# simple_breakout.net
KiCad netlist of a schematic drawn in EAGLE
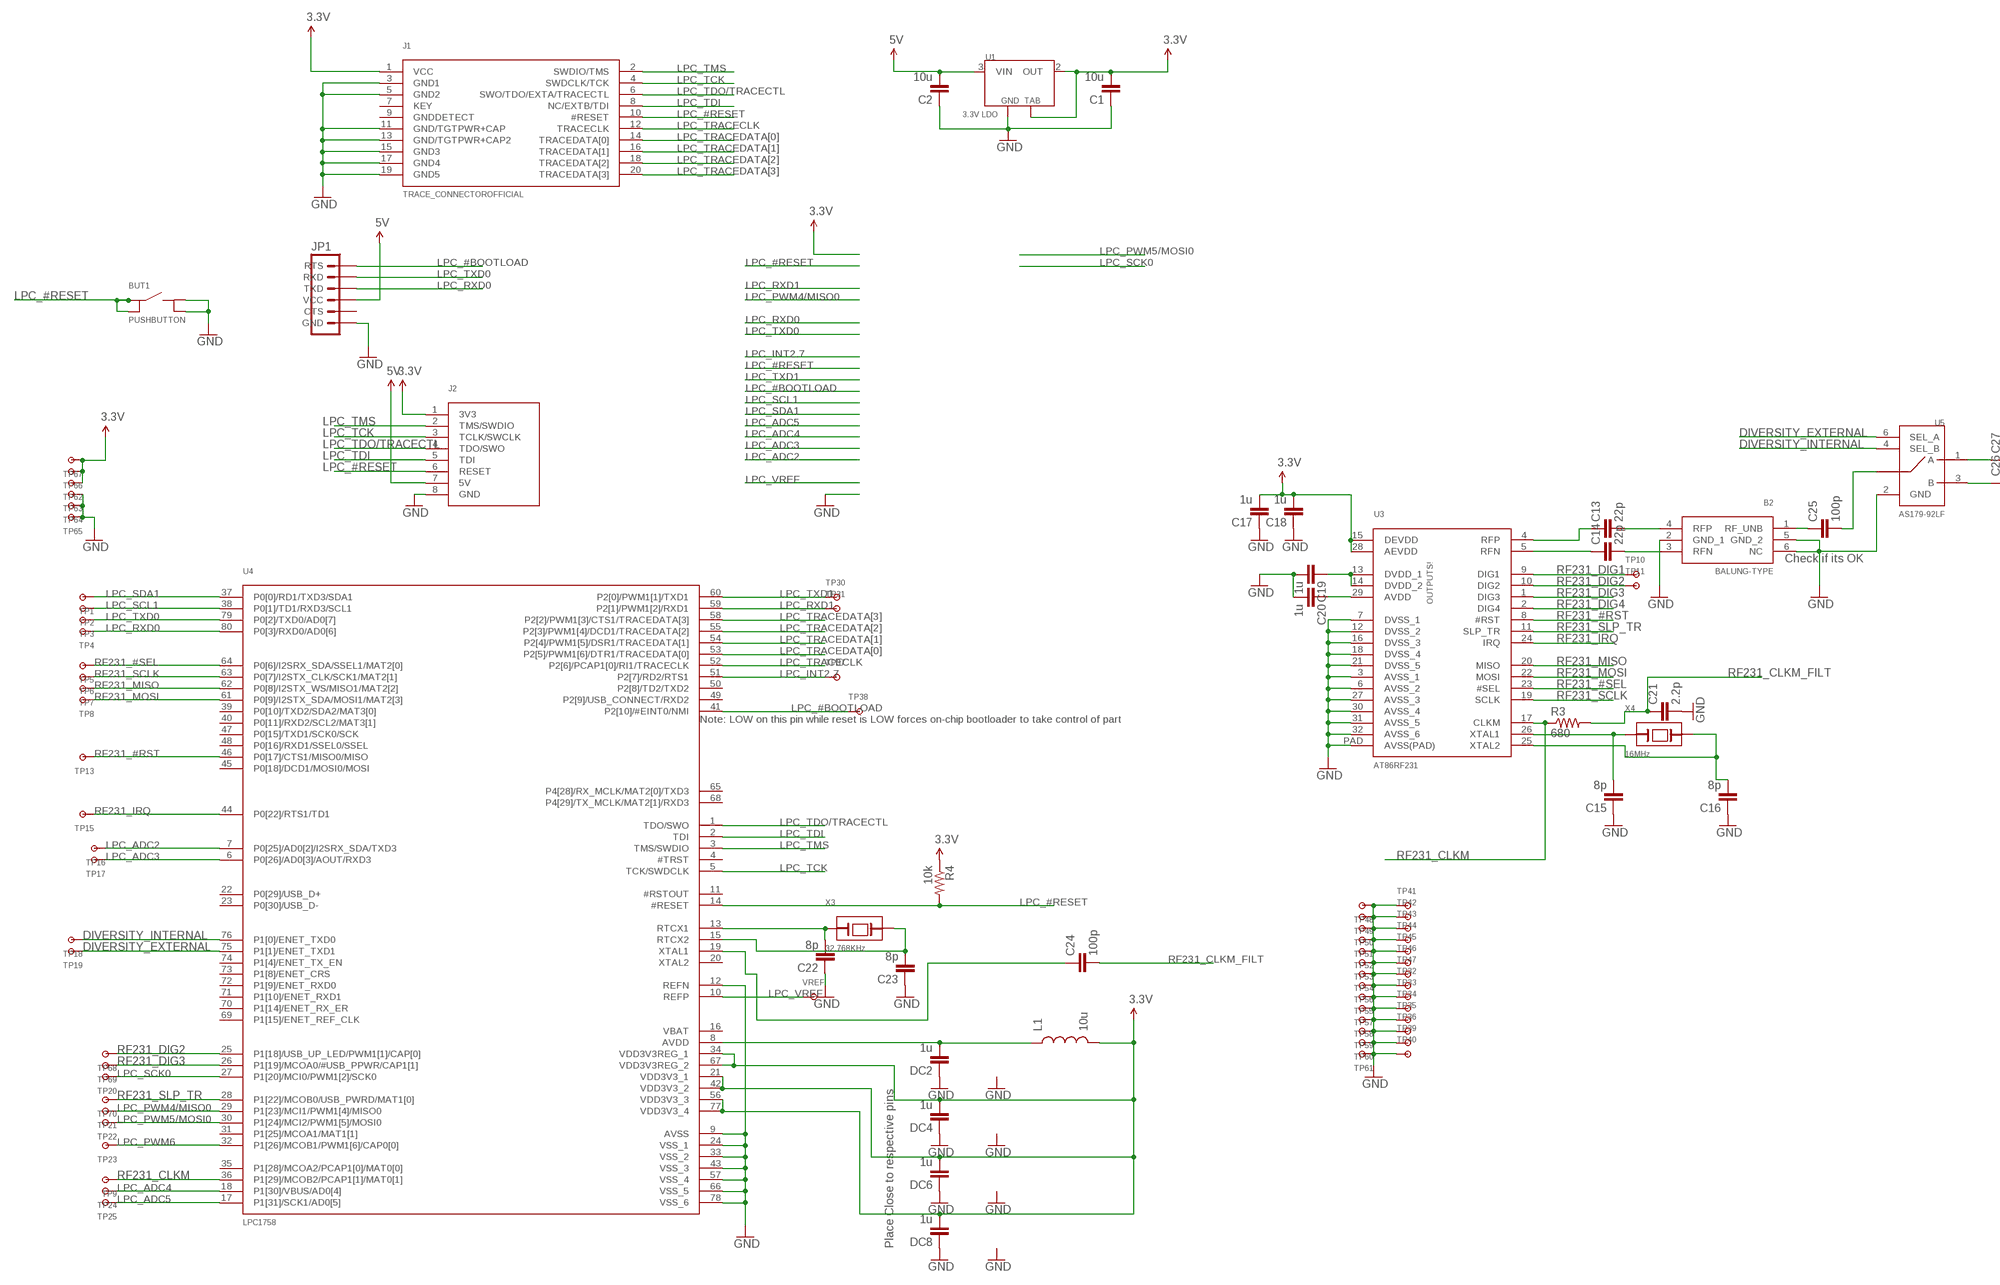
[diagram p0: schematic, sheet 1, part 1 of 2]
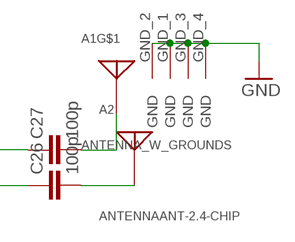
[diagram p1: schematic, sheet 1, part 2 of 2]

(export (version "E")
  (design (tool "Eeschema 10.0.6"))
  (components
    (comp (ref "A1")
      (value "ANTENNA_W_GROUNDS")
      (footprint "eagle-import:CONREVSMA003.031")
      (libsource (lib "eagle-import") (part "ANTENNA_W_GROUNDS"))
    )
    (comp (ref "A2")
      (value "ANTENNAANT-2.4-CHIP")
      (footprint "eagle-import:ANT-2.4-CHP")
      (libsource (lib "eagle-import") (part "ANTENNAANT-2.4-CHIP"))
    )
    (comp (ref "B2")
      (value "BALUNG-TYPE")
      (footprint "eagle-import:MURATA_LDB_BALUN")
      (libsource (lib "eagle-import") (part "BALUNG-TYPE"))
    )
    (comp (ref "BUT1")
      (value "PUSHBUTTON")
      (footprint "eagle-import:SMT_PUSHBUTTON")
      (libsource (lib "eagle-import") (part "PUSHBUTTON"))
    )
    (comp (ref "C1")
      (value "10u")
      (footprint "eagle-import:0805")
      (libsource (lib "eagle-import") (part "CAP0805"))
    )
    (comp (ref "C2")
      (value "10u")
      (footprint "eagle-import:0805")
      (libsource (lib "eagle-import") (part "CAP0805"))
    )
    (comp (ref "C13")
      (value "22p")
      (footprint "eagle-import:C0402")
      (libsource (lib "eagle-import") (part "CAP0402"))
    )
    (comp (ref "C14")
      (value "22p")
      (footprint "eagle-import:C0402")
      (libsource (lib "eagle-import") (part "CAP0402"))
    )
    (comp (ref "C15")
      (value "8p")
      (footprint "eagle-import:C0402")
      (libsource (lib "eagle-import") (part "CAP0402"))
    )
    (comp (ref "C16")
      (value "8p")
      (footprint "eagle-import:C0402")
      (libsource (lib "eagle-import") (part "CAP0402"))
    )
    (comp (ref "C17")
      (value "1u")
      (footprint "eagle-import:C0402")
      (libsource (lib "eagle-import") (part "CAP0402"))
    )
    (comp (ref "C18")
      (value "1u")
      (footprint "eagle-import:C0402")
      (libsource (lib "eagle-import") (part "CAP0402"))
    )
    (comp (ref "C19")
      (value "1u")
      (footprint "eagle-import:C0402")
      (libsource (lib "eagle-import") (part "CAP0402"))
    )
    (comp (ref "C20")
      (value "1u")
      (footprint "eagle-import:C0402")
      (libsource (lib "eagle-import") (part "CAP0402"))
    )
    (comp (ref "C21")
      (value "2.2p")
      (footprint "eagle-import:C0402")
      (libsource (lib "eagle-import") (part "CAP0402"))
    )
    (comp (ref "C22")
      (value "8p")
      (footprint "eagle-import:C0402")
      (libsource (lib "eagle-import") (part "CAP0402"))
    )
    (comp (ref "C23")
      (value "8p")
      (footprint "eagle-import:C0402")
      (libsource (lib "eagle-import") (part "CAP0402"))
    )
    (comp (ref "C24")
      (value "100p")
      (footprint "eagle-import:C0402")
      (libsource (lib "eagle-import") (part "CAP0402"))
    )
    (comp (ref "C25")
      (value "100p")
      (footprint "eagle-import:C0402")
      (libsource (lib "eagle-import") (part "CAP0402"))
    )
    (comp (ref "C26")
      (value "100p")
      (footprint "eagle-import:C0402")
      (libsource (lib "eagle-import") (part "CAP0402"))
    )
    (comp (ref "C27")
      (value "100p")
      (footprint "eagle-import:C0402")
      (libsource (lib "eagle-import") (part "CAP0402"))
    )
    (comp (ref "DC2")
      (value "1u")
      (footprint "eagle-import:C0402")
      (libsource (lib "eagle-import") (part "CAP0402"))
    )
    (comp (ref "DC4")
      (value "1u")
      (footprint "eagle-import:C0402")
      (libsource (lib "eagle-import") (part "CAP0402"))
    )
    (comp (ref "DC6")
      (value "1u")
      (footprint "eagle-import:C0402")
      (libsource (lib "eagle-import") (part "CAP0402"))
    )
    (comp (ref "DC8")
      (value "1u")
      (footprint "eagle-import:C0402")
      (libsource (lib "eagle-import") (part "CAP0402"))
    )
    (comp (ref "J1")
      (value "TRACE_CONNECTOROFFICIAL")
      (footprint "eagle-import:FTSH-110-01-L-DV")
      (libsource (lib "eagle-import") (part "TRACE_CONNECTOROFFICIAL"))
    )
    (comp (ref "J2")
      (value "LPCXPRESSO_JTAG")
      (footprint "eagle-import:1X08")
      (libsource (lib "eagle-import") (part "LPCXPRESSO_JTAG"))
    )
    (comp (ref "JP1")
      (value "FTDI_CABLESIP")
      (footprint "eagle-import:1X06")
      (libsource (lib "eagle-import") (part "FTDI_CABLESIP"))
    )
    (comp (ref "L1")
      (value "10u")
      (footprint "eagle-import:0603")
      (libsource (lib "eagle-import") (part "INDUCTOR0603"))
    )
    (comp (ref "R3")
      (value "680")
      (footprint "eagle-import:C0402")
      (libsource (lib "eagle-import") (part "RESISTOR0402"))
    )
    (comp (ref "R4")
      (value "10k")
      (footprint "eagle-import:C0402")
      (libsource (lib "eagle-import") (part "RESISTOR0402"))
    )
    (comp (ref "TP1")
      (value "TESTPOINT100MIL")
      (footprint "eagle-import:TESTPOINT-100MIL")
      (libsource (lib "eagle-import") (part "TESTPOINT100MIL"))
    )
    (comp (ref "TP2")
      (value "TESTPOINT100MIL")
      (footprint "eagle-import:TESTPOINT-100MIL")
      (libsource (lib "eagle-import") (part "TESTPOINT100MIL"))
    )
    (comp (ref "TP3")
      (value "TESTPOINT100MIL")
      (footprint "eagle-import:TESTPOINT-100MIL")
      (libsource (lib "eagle-import") (part "TESTPOINT100MIL"))
    )
    (comp (ref "TP4")
      (value "TESTPOINT100MIL")
      (footprint "eagle-import:TESTPOINT-100MIL")
      (libsource (lib "eagle-import") (part "TESTPOINT100MIL"))
    )
    (comp (ref "TP5")
      (value "TESTPOINT100MIL")
      (footprint "eagle-import:TESTPOINT-100MIL")
      (libsource (lib "eagle-import") (part "TESTPOINT100MIL"))
    )
    (comp (ref "TP6")
      (value "TESTPOINT100MIL")
      (footprint "eagle-import:TESTPOINT-100MIL")
      (libsource (lib "eagle-import") (part "TESTPOINT100MIL"))
    )
    (comp (ref "TP7")
      (value "TESTPOINT100MIL")
      (footprint "eagle-import:TESTPOINT-100MIL")
      (libsource (lib "eagle-import") (part "TESTPOINT100MIL"))
    )
    (comp (ref "TP8")
      (value "TESTPOINT100MIL")
      (footprint "eagle-import:TESTPOINT-100MIL")
      (libsource (lib "eagle-import") (part "TESTPOINT100MIL"))
    )
    (comp (ref "TP9")
      (value "TESTPOINT100MIL")
      (footprint "eagle-import:TESTPOINT-100MIL")
      (libsource (lib "eagle-import") (part "TESTPOINT100MIL"))
    )
    (comp (ref "TP10")
      (value "TESTPOINT100MIL")
      (footprint "eagle-import:TESTPOINT-100MIL")
      (libsource (lib "eagle-import") (part "TESTPOINT100MIL"))
    )
    (comp (ref "TP11")
      (value "TESTPOINT100MIL")
      (footprint "eagle-import:TESTPOINT-100MIL")
      (libsource (lib "eagle-import") (part "TESTPOINT100MIL"))
    )
    (comp (ref "TP13")
      (value "TESTPOINT100MIL")
      (footprint "eagle-import:TESTPOINT-100MIL")
      (libsource (lib "eagle-import") (part "TESTPOINT100MIL"))
    )
    (comp (ref "TP15")
      (value "TESTPOINT100MIL")
      (footprint "eagle-import:TESTPOINT-100MIL")
      (libsource (lib "eagle-import") (part "TESTPOINT100MIL"))
    )
    (comp (ref "TP16")
      (value "TESTPOINT100MIL")
      (footprint "eagle-import:TESTPOINT-100MIL")
      (libsource (lib "eagle-import") (part "TESTPOINT100MIL"))
    )
    (comp (ref "TP17")
      (value "TESTPOINT100MIL")
      (footprint "eagle-import:TESTPOINT-100MIL")
      (libsource (lib "eagle-import") (part "TESTPOINT100MIL"))
    )
    (comp (ref "TP18")
      (value "TESTPOINT100MIL")
      (footprint "eagle-import:TESTPOINT-100MIL")
      (libsource (lib "eagle-import") (part "TESTPOINT100MIL"))
    )
    (comp (ref "TP19")
      (value "TESTPOINT100MIL")
      (footprint "eagle-import:TESTPOINT-100MIL")
      (libsource (lib "eagle-import") (part "TESTPOINT100MIL"))
    )
    (comp (ref "TP20")
      (value "TESTPOINT100MIL")
      (footprint "eagle-import:TESTPOINT-100MIL")
      (libsource (lib "eagle-import") (part "TESTPOINT100MIL"))
    )
    (comp (ref "TP21")
      (value "TESTPOINT100MIL")
      (footprint "eagle-import:TESTPOINT-100MIL")
      (libsource (lib "eagle-import") (part "TESTPOINT100MIL"))
    )
    (comp (ref "TP22")
      (value "TESTPOINT100MIL")
      (footprint "eagle-import:TESTPOINT-100MIL")
      (libsource (lib "eagle-import") (part "TESTPOINT100MIL"))
    )
    (comp (ref "TP23")
      (value "TESTPOINT100MIL")
      (footprint "eagle-import:TESTPOINT-100MIL")
      (libsource (lib "eagle-import") (part "TESTPOINT100MIL"))
    )
    (comp (ref "TP24")
      (value "TESTPOINT100MIL")
      (footprint "eagle-import:TESTPOINT-100MIL")
      (libsource (lib "eagle-import") (part "TESTPOINT100MIL"))
    )
    (comp (ref "TP25")
      (value "TESTPOINT100MIL")
      (footprint "eagle-import:TESTPOINT-100MIL")
      (libsource (lib "eagle-import") (part "TESTPOINT100MIL"))
    )
    (comp (ref "TP30")
      (value "TESTPOINT100MIL")
      (footprint "eagle-import:TESTPOINT-100MIL")
      (libsource (lib "eagle-import") (part "TESTPOINT100MIL"))
    )
    (comp (ref "TP31")
      (value "TESTPOINT100MIL")
      (footprint "eagle-import:TESTPOINT-100MIL")
      (libsource (lib "eagle-import") (part "TESTPOINT100MIL"))
    )
    (comp (ref "TP32")
      (value "TESTPOINTSMALLEST")
      (footprint "eagle-import:TESTPOINT")
      (libsource (lib "eagle-import") (part "TESTPOINTSMALLEST"))
    )
    (comp (ref "TP33")
      (value "TESTPOINTSMALLEST")
      (footprint "eagle-import:TESTPOINT")
      (libsource (lib "eagle-import") (part "TESTPOINTSMALLEST"))
    )
    (comp (ref "TP34")
      (value "TESTPOINTSMALLEST")
      (footprint "eagle-import:TESTPOINT")
      (libsource (lib "eagle-import") (part "TESTPOINTSMALLEST"))
    )
    (comp (ref "TP35")
      (value "TESTPOINTSMALLEST")
      (footprint "eagle-import:TESTPOINT")
      (libsource (lib "eagle-import") (part "TESTPOINTSMALLEST"))
    )
    (comp (ref "TP36")
      (value "TESTPOINTSMALLEST")
      (footprint "eagle-import:TESTPOINT")
      (libsource (lib "eagle-import") (part "TESTPOINTSMALLEST"))
    )
    (comp (ref "TP37")
      (value "TESTPOINT100MIL")
      (footprint "eagle-import:TESTPOINT-100MIL")
      (libsource (lib "eagle-import") (part "TESTPOINT100MIL"))
    )
    (comp (ref "TP38")
      (value "TESTPOINT100MIL")
      (footprint "eagle-import:TESTPOINT-100MIL")
      (libsource (lib "eagle-import") (part "TESTPOINT100MIL"))
    )
    (comp (ref "TP39")
      (value "TESTPOINTSMALLEST")
      (footprint "eagle-import:TESTPOINT")
      (libsource (lib "eagle-import") (part "TESTPOINTSMALLEST"))
    )
    (comp (ref "TP40")
      (value "TESTPOINTSMALLEST")
      (footprint "eagle-import:TESTPOINT")
      (libsource (lib "eagle-import") (part "TESTPOINTSMALLEST"))
    )
    (comp (ref "TP41")
      (value "TESTPOINTSMALLEST")
      (footprint "eagle-import:TESTPOINT")
      (libsource (lib "eagle-import") (part "TESTPOINTSMALLEST"))
    )
    (comp (ref "TP42")
      (value "TESTPOINTSMALLEST")
      (footprint "eagle-import:TESTPOINT")
      (libsource (lib "eagle-import") (part "TESTPOINTSMALLEST"))
    )
    (comp (ref "TP43")
      (value "TESTPOINTSMALLEST")
      (footprint "eagle-import:TESTPOINT")
      (libsource (lib "eagle-import") (part "TESTPOINTSMALLEST"))
    )
    (comp (ref "TP44")
      (value "TESTPOINTSMALLEST")
      (footprint "eagle-import:TESTPOINT")
      (libsource (lib "eagle-import") (part "TESTPOINTSMALLEST"))
    )
    (comp (ref "TP45")
      (value "TESTPOINTSMALLEST")
      (footprint "eagle-import:TESTPOINT")
      (libsource (lib "eagle-import") (part "TESTPOINTSMALLEST"))
    )
    (comp (ref "TP46")
      (value "TESTPOINTSMALLEST")
      (footprint "eagle-import:TESTPOINT")
      (libsource (lib "eagle-import") (part "TESTPOINTSMALLEST"))
    )
    (comp (ref "TP47")
      (value "TESTPOINTSMALLEST")
      (footprint "eagle-import:TESTPOINT")
      (libsource (lib "eagle-import") (part "TESTPOINTSMALLEST"))
    )
    (comp (ref "TP48")
      (value "TESTPOINTSMALLEST")
      (footprint "eagle-import:TESTPOINT")
      (libsource (lib "eagle-import") (part "TESTPOINTSMALLEST"))
    )
    (comp (ref "TP49")
      (value "TESTPOINTSMALLEST")
      (footprint "eagle-import:TESTPOINT")
      (libsource (lib "eagle-import") (part "TESTPOINTSMALLEST"))
    )
    (comp (ref "TP50")
      (value "TESTPOINTSMALLEST")
      (footprint "eagle-import:TESTPOINT")
      (libsource (lib "eagle-import") (part "TESTPOINTSMALLEST"))
    )
    (comp (ref "TP51")
      (value "TESTPOINTSMALLEST")
      (footprint "eagle-import:TESTPOINT")
      (libsource (lib "eagle-import") (part "TESTPOINTSMALLEST"))
    )
    (comp (ref "TP52")
      (value "TESTPOINTSMALLEST")
      (footprint "eagle-import:TESTPOINT")
      (libsource (lib "eagle-import") (part "TESTPOINTSMALLEST"))
    )
    (comp (ref "TP53")
      (value "TESTPOINTSMALLEST")
      (footprint "eagle-import:TESTPOINT")
      (libsource (lib "eagle-import") (part "TESTPOINTSMALLEST"))
    )
    (comp (ref "TP54")
      (value "TESTPOINTSMALLEST")
      (footprint "eagle-import:TESTPOINT")
      (libsource (lib "eagle-import") (part "TESTPOINTSMALLEST"))
    )
    (comp (ref "TP55")
      (value "TESTPOINTSMALLEST")
      (footprint "eagle-import:TESTPOINT")
      (libsource (lib "eagle-import") (part "TESTPOINTSMALLEST"))
    )
    (comp (ref "TP56")
      (value "TESTPOINTSMALLEST")
      (footprint "eagle-import:TESTPOINT")
      (libsource (lib "eagle-import") (part "TESTPOINTSMALLEST"))
    )
    (comp (ref "TP57")
      (value "TESTPOINTSMALLEST")
      (footprint "eagle-import:TESTPOINT")
      (libsource (lib "eagle-import") (part "TESTPOINTSMALLEST"))
    )
    (comp (ref "TP58")
      (value "TESTPOINTSMALLEST")
      (footprint "eagle-import:TESTPOINT")
      (libsource (lib "eagle-import") (part "TESTPOINTSMALLEST"))
    )
    (comp (ref "TP59")
      (value "TESTPOINTSMALLEST")
      (footprint "eagle-import:TESTPOINT")
      (libsource (lib "eagle-import") (part "TESTPOINTSMALLEST"))
    )
    (comp (ref "TP60")
      (value "TESTPOINTSMALLEST")
      (footprint "eagle-import:TESTPOINT")
      (libsource (lib "eagle-import") (part "TESTPOINTSMALLEST"))
    )
    (comp (ref "TP61")
      (value "TESTPOINTSMALLEST")
      (footprint "eagle-import:TESTPOINT")
      (libsource (lib "eagle-import") (part "TESTPOINTSMALLEST"))
    )
    (comp (ref "TP62")
      (value "TESTPOINT100MIL")
      (footprint "eagle-import:TESTPOINT-100MIL")
      (libsource (lib "eagle-import") (part "TESTPOINT100MIL"))
    )
    (comp (ref "TP63")
      (value "TESTPOINT100MIL")
      (footprint "eagle-import:TESTPOINT-100MIL")
      (libsource (lib "eagle-import") (part "TESTPOINT100MIL"))
    )
    (comp (ref "TP64")
      (value "TESTPOINT100MIL")
      (footprint "eagle-import:TESTPOINT-100MIL")
      (libsource (lib "eagle-import") (part "TESTPOINT100MIL"))
    )
    (comp (ref "TP65")
      (value "TESTPOINT100MIL")
      (footprint "eagle-import:TESTPOINT-100MIL")
      (libsource (lib "eagle-import") (part "TESTPOINT100MIL"))
    )
    (comp (ref "TP66")
      (value "TESTPOINT100MIL")
      (footprint "eagle-import:TESTPOINT-100MIL")
      (libsource (lib "eagle-import") (part "TESTPOINT100MIL"))
    )
    (comp (ref "TP67")
      (value "TESTPOINT100MIL")
      (footprint "eagle-import:TESTPOINT-100MIL")
      (libsource (lib "eagle-import") (part "TESTPOINT100MIL"))
    )
    (comp (ref "TP68")
      (value "TESTPOINT100MIL")
      (footprint "eagle-import:TESTPOINT-100MIL")
      (libsource (lib "eagle-import") (part "TESTPOINT100MIL"))
    )
    (comp (ref "TP69")
      (value "TESTPOINT100MIL")
      (footprint "eagle-import:TESTPOINT-100MIL")
      (libsource (lib "eagle-import") (part "TESTPOINT100MIL"))
    )
    (comp (ref "TP70")
      (value "TESTPOINT100MIL")
      (footprint "eagle-import:TESTPOINT-100MIL")
      (libsource (lib "eagle-import") (part "TESTPOINT100MIL"))
    )
    (comp (ref "U1")
      (value "3.3V LDO")
      (footprint "eagle-import:SOT223")
      (libsource (lib "eagle-import") (part "NX1117C"))
    )
    (comp (ref "U3")
      (value "AT86RF231")
      (footprint "eagle-import:ATRF231_32QN2")
      (libsource (lib "eagle-import") (part "AT86RF231"))
    )
    (comp (ref "U4")
      (value "LPC1758")
      (footprint "eagle-import:LPC1758_LQFP80")
      (libsource (lib "eagle-import") (part "LPC1758"))
    )
    (comp (ref "U5")
      (value "AS179-92LF")
      (footprint "eagle-import:SC-70")
      (libsource (lib "eagle-import") (part "AS179-92LF"))
    )
    (comp (ref "VREF")
      (value "TESTPOINT100MIL")
      (footprint "eagle-import:TESTPOINT-100MIL")
      (libsource (lib "eagle-import") (part "TESTPOINT100MIL"))
    )
    (comp (ref "X3")
      (value "32.768KHz")
      (footprint "eagle-import:ABS07")
      (libsource (lib "eagle-import") (part "XTALABS07"))
    )
    (comp (ref "X4")
      (value "16MHz")
      (footprint "eagle-import:CX3225SA")
      (libsource (lib "eagle-import") (part "XTALCX3225SA"))
    )
  )
  (nets
    (net (code "1") (name "/DIVERSITY_EXTERNAL") (class "Default")
      (node (ref "TP19") (pin "2") (pinfunction "P$1_2") (pintype "bidirectional"))
      (node (ref "U4") (pin "75") (pinfunction "P1[1]/ENET_TXD1_75") (pintype "bidirectional"))
      (node (ref "U5") (pin "6") (pinfunction "SEL_A_6") (pintype "bidirectional"))
    )
    (net (code "2") (name "/DIVERSITY_INTERNAL") (class "Default")
      (node (ref "TP18") (pin "2") (pinfunction "P$1_2") (pintype "bidirectional"))
      (node (ref "U4") (pin "76") (pinfunction "P1[0]/ENET_TXD0_76") (pintype "bidirectional"))
      (node (ref "U5") (pin "4") (pinfunction "SEL_B_4") (pintype "bidirectional"))
    )
    (net (code "3") (name "/LPC_#BOOTLOAD") (class "Default")
      (node (ref "JP1") (pin "6") (pinfunction "RTS_6") (pintype "passive"))
      (node (ref "TP38") (pin "2") (pinfunction "P$1_2") (pintype "bidirectional"))
      (node (ref "U4") (pin "41") (pinfunction "P2[10]/#EINT0/NMI_41") (pintype "bidirectional"))
    )
    (net (code "4") (name "/LPC_#RESET") (class "Default")
      (node (ref "BUT1") (pin "1@1") (pinfunction "1_1@1") (pintype "bidirectional"))
      (node (ref "BUT1") (pin "1@2") (pinfunction "1_1@2") (pintype "bidirectional"))
      (node (ref "J1") (pin "10") (pinfunction "#RESET_10") (pintype "bidirectional"))
      (node (ref "J2") (pin "6") (pinfunction "RESET_6") (pintype "bidirectional"))
      (node (ref "R4") (pin "2") (pinfunction "2_2") (pintype "passive"))
      (node (ref "U4") (pin "14") (pinfunction "#RESET_14") (pintype "bidirectional"))
    )
    (net (code "5") (name "/LPC_ADC2") (class "Default")
      (node (ref "TP16") (pin "2") (pinfunction "P$1_2") (pintype "bidirectional"))
      (node (ref "U4") (pin "7") (pinfunction "P0[25]/AD0[2]/I2SRX_SDA/TXD3_7") (pintype "bidirectional"))
    )
    (net (code "6") (name "/LPC_ADC3") (class "Default")
      (node (ref "TP17") (pin "2") (pinfunction "P$1_2") (pintype "bidirectional"))
      (node (ref "U4") (pin "6") (pinfunction "P0[26]/AD0[3]/AOUT/RXD3_6") (pintype "bidirectional"))
    )
    (net (code "7") (name "/LPC_ADC4") (class "Default")
      (node (ref "TP24") (pin "2") (pinfunction "P$1_2") (pintype "bidirectional"))
      (node (ref "U4") (pin "18") (pinfunction "P1[30]/VBUS/AD0[4]_18") (pintype "bidirectional"))
    )
    (net (code "8") (name "/LPC_ADC5") (class "Default")
      (node (ref "TP25") (pin "2") (pinfunction "P$1_2") (pintype "bidirectional"))
      (node (ref "U4") (pin "17") (pinfunction "P1[31]/SCK1/AD0[5]_17") (pintype "bidirectional"))
    )
    (net (code "9") (name "/LPC_INT2.7") (class "Default")
      (node (ref "TP37") (pin "2") (pinfunction "P$1_2") (pintype "bidirectional"))
      (node (ref "U4") (pin "51") (pinfunction "P2[7]/RD2/RTS1_51") (pintype "bidirectional"))
    )
    (net (code "10") (name "/LPC_PWM4{slash}MISO0") (class "Default")
      (node (ref "TP21") (pin "2") (pinfunction "P$1_2") (pintype "bidirectional"))
      (node (ref "U4") (pin "29") (pinfunction "P1[23]/MCI1/PWM1[4]/MISO0_29") (pintype "bidirectional"))
    )
    (net (code "11") (name "/LPC_PWM5{slash}MOSI0") (class "Default")
      (node (ref "TP22") (pin "2") (pinfunction "P$1_2") (pintype "bidirectional"))
      (node (ref "U4") (pin "30") (pinfunction "P1[24]/MCI2/PWM1[5]/MOSI0_30") (pintype "bidirectional"))
    )
    (net (code "12") (name "/LPC_PWM6") (class "Default")
      (node (ref "TP23") (pin "2") (pinfunction "P$1_2") (pintype "bidirectional"))
      (node (ref "U4") (pin "32") (pinfunction "P1[26]/MCOB1/PWM1[6]/CAP0[0]_32") (pintype "bidirectional"))
    )
    (net (code "13") (name "/LPC_RXD0") (class "Default")
      (node (ref "JP1") (pin "4") (pinfunction "TXD_4") (pintype "passive"))
      (node (ref "TP4") (pin "2") (pinfunction "P$1_2") (pintype "bidirectional"))
      (node (ref "U4") (pin "80") (pinfunction "P0[3]/RXD0/AD0[6]_80") (pintype "bidirectional"))
    )
    (net (code "14") (name "/LPC_RXD1") (class "Default")
      (node (ref "TP31") (pin "2") (pinfunction "P$1_2") (pintype "bidirectional"))
      (node (ref "U4") (pin "59") (pinfunction "P2[1]/PWM1[2]/RXD1_59") (pintype "bidirectional"))
    )
    (net (code "15") (name "/LPC_SCK0") (class "Default")
      (node (ref "TP20") (pin "2") (pinfunction "P$1_2") (pintype "bidirectional"))
      (node (ref "U4") (pin "27") (pinfunction "P1[20]/MCI0/PWM1[2]/SCK0_27") (pintype "bidirectional"))
    )
    (net (code "16") (name "/LPC_SCL1") (class "Default")
      (node (ref "TP2") (pin "2") (pinfunction "P$1_2") (pintype "bidirectional"))
      (node (ref "U4") (pin "38") (pinfunction "P0[1]/TD1/RXD3/SCL1_38") (pintype "bidirectional"))
    )
    (net (code "17") (name "/LPC_SDA1") (class "Default")
      (node (ref "TP1") (pin "2") (pinfunction "P$1_2") (pintype "bidirectional"))
      (node (ref "U4") (pin "37") (pinfunction "P0[0]/RD1/TXD3/SDA1_37") (pintype "bidirectional"))
    )
    (net (code "18") (name "/LPC_TCK") (class "Default")
      (node (ref "J1") (pin "4") (pinfunction "SWDCLK/TCK_4") (pintype "bidirectional"))
      (node (ref "J2") (pin "3") (pinfunction "TCLK/SWCLK_3") (pintype "bidirectional"))
      (node (ref "U4") (pin "5") (pinfunction "TCK/SWDCLK_5") (pintype "bidirectional"))
    )
    (net (code "19") (name "/LPC_TDI") (class "Default")
      (node (ref "J1") (pin "8") (pinfunction "NC/EXTB/TDI_8") (pintype "bidirectional"))
      (node (ref "J2") (pin "5") (pinfunction "TDI_5") (pintype "bidirectional"))
      (node (ref "U4") (pin "2") (pinfunction "TDI_2") (pintype "bidirectional"))
    )
    (net (code "20") (name "/LPC_TDO{slash}TRACECTL") (class "Default")
      (node (ref "J1") (pin "6") (pinfunction "SWO/TDO/EXTA/TRACECTL_6") (pintype "bidirectional"))
      (node (ref "J2") (pin "4") (pinfunction "TDO/SWO_4") (pintype "bidirectional"))
      (node (ref "U4") (pin "1") (pinfunction "TDO/SWO_1") (pintype "bidirectional"))
    )
    (net (code "21") (name "/LPC_TMS") (class "Default")
      (node (ref "J1") (pin "2") (pinfunction "SWDIO/TMS_2") (pintype "bidirectional"))
      (node (ref "J2") (pin "2") (pinfunction "TMS/SWDIO_2") (pintype "bidirectional"))
      (node (ref "U4") (pin "3") (pinfunction "TMS/SWDIO_3") (pintype "bidirectional"))
    )
    (net (code "22") (name "/LPC_TRACECLK") (class "Default")
      (node (ref "J1") (pin "12") (pinfunction "TRACECLK_12") (pintype "bidirectional"))
      (node (ref "U4") (pin "52") (pinfunction "P2[6]/PCAP1[0]/RI1/TRACECLK_52") (pintype "bidirectional"))
    )
    (net (code "23") (name "/LPC_TRACEDATA[0]") (class "Default")
      (node (ref "J1") (pin "14") (pinfunction "TRACEDATA[0]_14") (pintype "bidirectional"))
      (node (ref "U4") (pin "53") (pinfunction "P2[5]/PWM1[6]/DTR1/TRACEDATA[0]_53") (pintype "bidirectional"))
    )
    (net (code "24") (name "/LPC_TRACEDATA[1]") (class "Default")
      (node (ref "J1") (pin "16") (pinfunction "TRACEDATA[1]_16") (pintype "bidirectional"))
      (node (ref "U4") (pin "54") (pinfunction "P2[4]/PWM1[5]/DSR1/TRACEDATA[1]_54") (pintype "bidirectional"))
    )
    (net (code "25") (name "/LPC_TRACEDATA[2]") (class "Default")
      (node (ref "J1") (pin "18") (pinfunction "TRACEDATA[2]_18") (pintype "bidirectional"))
      (node (ref "U4") (pin "55") (pinfunction "P2[3]/PWM1[4]/DCD1/TRACEDATA[2]_55") (pintype "bidirectional"))
    )
    (net (code "26") (name "/LPC_TRACEDATA[3]") (class "Default")
      (node (ref "J1") (pin "20") (pinfunction "TRACEDATA[3]_20") (pintype "bidirectional"))
      (node (ref "U4") (pin "58") (pinfunction "P2[2]/PWM1[3]/CTS1/TRACEDATA[3]_58") (pintype "bidirectional"))
    )
    (net (code "27") (name "/LPC_TXD0") (class "Default")
      (node (ref "JP1") (pin "5") (pinfunction "RXD_5") (pintype "passive"))
      (node (ref "TP3") (pin "2") (pinfunction "P$1_2") (pintype "bidirectional"))
      (node (ref "U4") (pin "79") (pinfunction "P0[2]/TXD0/AD0[7]_79") (pintype "bidirectional"))
    )
    (net (code "28") (name "/LPC_TXD1") (class "Default")
      (node (ref "TP30") (pin "2") (pinfunction "P$1_2") (pintype "bidirectional"))
      (node (ref "U4") (pin "60") (pinfunction "P2[0]/PWM1[1]/TXD1_60") (pintype "bidirectional"))
    )
    (net (code "29") (name "/LPC_VREF") (class "Default")
      (node (ref "U4") (pin "10") (pinfunction "REFP_10") (pintype "bidirectional"))
      (node (ref "VREF") (pin "2") (pinfunction "P$1_2") (pintype "bidirectional"))
    )
    (net (code "30") (name "/RF231_#RST") (class "Default")
      (node (ref "TP13") (pin "2") (pinfunction "P$1_2") (pintype "bidirectional"))
      (node (ref "U3") (pin "8") (pinfunction "#RST_8") (pintype "bidirectional"))
      (node (ref "U4") (pin "46") (pinfunction "P0[17]/CTS1/MISO0/MISO_46") (pintype "bidirectional"))
    )
    (net (code "31") (name "/RF231_#SEL") (class "Default")
      (node (ref "TP5") (pin "2") (pinfunction "P$1_2") (pintype "bidirectional"))
      (node (ref "U3") (pin "23") (pinfunction "#SEL_23") (pintype "bidirectional"))
      (node (ref "U4") (pin "64") (pinfunction "P0[6]/I2SRX_SDA/SSEL1/MAT2[0]_64") (pintype "bidirectional"))
    )
    (net (code "32") (name "/RF231_CLKM") (class "Default")
      (node (ref "R3") (pin "1") (pinfunction "1_1") (pintype "passive"))
      (node (ref "TP9") (pin "2") (pinfunction "P$1_2") (pintype "bidirectional"))
      (node (ref "U3") (pin "17") (pinfunction "CLKM_17") (pintype "bidirectional"))
      (node (ref "U4") (pin "36") (pinfunction "P1[29]/MCOB2/PCAP1[1]/MAT0[1]_36") (pintype "bidirectional"))
    )
    (net (code "33") (name "/RF231_CLKM_FILT") (class "Default")
      (node (ref "C21") (pin "1") (pinfunction "1_1") (pintype "passive"))
      (node (ref "C24") (pin "2") (pinfunction "2_2") (pintype "passive"))
      (node (ref "R3") (pin "2") (pinfunction "2_2") (pintype "passive"))
    )
    (net (code "34") (name "/RF231_DIG1") (class "Default")
      (node (ref "TP10") (pin "2") (pinfunction "P$1_2") (pintype "bidirectional"))
      (node (ref "U3") (pin "9") (pinfunction "DIG1_9") (pintype "bidirectional"))
    )
    (net (code "35") (name "/RF231_DIG2") (class "Default")
      (node (ref "TP11") (pin "2") (pinfunction "P$1_2") (pintype "bidirectional"))
      (node (ref "TP68") (pin "2") (pinfunction "P$1_2") (pintype "bidirectional"))
      (node (ref "U3") (pin "10") (pinfunction "DIG2_10") (pintype "bidirectional"))
      (node (ref "U4") (pin "25") (pinfunction "P1[18]/USB_UP_LED/PWM1[1]/CAP[0]_25") (pintype "bidirectional"))
    )
    (net (code "36") (name "/RF231_DIG3") (class "Default")
      (node (ref "TP69") (pin "2") (pinfunction "P$1_2") (pintype "bidirectional"))
      (node (ref "U3") (pin "1") (pinfunction "DIG3_1") (pintype "bidirectional"))
      (node (ref "U4") (pin "26") (pinfunction "P1[19]/MCOA0/#USB_PPWR/CAP1[1]_26") (pintype "bidirectional"))
    )
    (net (code "37") (name "/RF231_DIG4") (class "Default")
      (node (ref "U3") (pin "2") (pinfunction "DIG4_2") (pintype "bidirectional"))
    )
    (net (code "38") (name "/RF231_IRQ") (class "Default")
      (node (ref "TP15") (pin "2") (pinfunction "P$1_2") (pintype "bidirectional"))
      (node (ref "U3") (pin "24") (pinfunction "IRQ_24") (pintype "bidirectional"))
      (node (ref "U4") (pin "44") (pinfunction "P0[22]/RTS1/TD1_44") (pintype "bidirectional"))
    )
    (net (code "39") (name "/RF231_MISO") (class "Default")
      (node (ref "TP7") (pin "2") (pinfunction "P$1_2") (pintype "bidirectional"))
      (node (ref "U3") (pin "20") (pinfunction "MISO_20") (pintype "bidirectional"))
      (node (ref "U4") (pin "62") (pinfunction "P0[8]/I2STX_WS/MISO1/MAT2[2]_62") (pintype "bidirectional"))
    )
    (net (code "40") (name "/RF231_MOSI") (class "Default")
      (node (ref "TP8") (pin "2") (pinfunction "P$1_2") (pintype "bidirectional"))
      (node (ref "U3") (pin "22") (pinfunction "MOSI_22") (pintype "bidirectional"))
      (node (ref "U4") (pin "61") (pinfunction "P0[9]/I2STX_SDA/MOSI1/MAT2[3]_61") (pintype "bidirectional"))
    )
    (net (code "41") (name "/RF231_SCLK") (class "Default")
      (node (ref "TP6") (pin "2") (pinfunction "P$1_2") (pintype "bidirectional"))
      (node (ref "U3") (pin "19") (pinfunction "SCLK_19") (pintype "bidirectional"))
      (node (ref "U4") (pin "63") (pinfunction "P0[7]/I2STX_CLK/SCK1/MAT2[1]_63") (pintype "bidirectional"))
    )
    (net (code "42") (name "/RF231_SLP_TR") (class "Default")
      (node (ref "TP70") (pin "2") (pinfunction "P$1_2") (pintype "bidirectional"))
      (node (ref "U3") (pin "11") (pinfunction "SLP_TR_11") (pintype "bidirectional"))
      (node (ref "U4") (pin "28") (pinfunction "P1[22]/MCOB0/USB_PWRD/MAT1[0]_28") (pintype "bidirectional"))
    )
    (net (code "43") (name "3.3V") (class "Default")
      (node (ref "C1") (pin "2") (pinfunction "2_2") (pintype "passive"))
      (node (ref "C17") (pin "2") (pinfunction "2_2") (pintype "passive"))
      (node (ref "C18") (pin "2") (pinfunction "2_2") (pintype "passive"))
      (node (ref "DC4") (pin "2") (pinfunction "2_2") (pintype "passive"))
      (node (ref "DC6") (pin "2") (pinfunction "2_2") (pintype "passive"))
      (node (ref "DC8") (pin "2") (pinfunction "2_2") (pintype "passive"))
      (node (ref "J1") (pin "1") (pinfunction "VCC_1") (pintype "bidirectional"))
      (node (ref "J2") (pin "1") (pinfunction "3V3_1") (pintype "bidirectional"))
      (node (ref "L1") (pin "2") (pinfunction "2_2") (pintype "passive"))
      (node (ref "R4") (pin "1") (pinfunction "1_1") (pintype "passive"))
      (node (ref "TP62") (pin "2") (pinfunction "P$1_2") (pintype "bidirectional"))
      (node (ref "TP66") (pin "2") (pinfunction "P$1_2") (pintype "bidirectional"))
      (node (ref "TP67") (pin "2") (pinfunction "P$1_2") (pintype "bidirectional"))
      (node (ref "U1") (pin "2") (pinfunction "OUT_2") (pintype "bidirectional"))
      (node (ref "U1") (pin "4") (pinfunction "TAB_4") (pintype "bidirectional"))
      (node (ref "U3") (pin "15") (pinfunction "DEVDD_15") (pintype "bidirectional"))
      (node (ref "U3") (pin "28") (pinfunction "AEVDD_28") (pintype "bidirectional"))
      (node (ref "U4") (pin "21") (pinfunction "VDD3V3_1_21") (pintype "bidirectional"))
      (node (ref "U4") (pin "34") (pinfunction "VDD3V3REG_1_34") (pintype "bidirectional"))
      (node (ref "U4") (pin "42") (pinfunction "VDD3V3_2_42") (pintype "bidirectional"))
      (node (ref "U4") (pin "56") (pinfunction "VDD3V3_3_56") (pintype "bidirectional"))
      (node (ref "U4") (pin "67") (pinfunction "VDD3V3REG_2_67") (pintype "bidirectional"))
      (node (ref "U4") (pin "77") (pinfunction "VDD3V3_4_77") (pintype "bidirectional"))
    )
    (net (code "44") (name "5V") (class "Default")
      (node (ref "C2") (pin "2") (pinfunction "2_2") (pintype "passive"))
      (node (ref "J2") (pin "7") (pinfunction "5V_7") (pintype "bidirectional"))
      (node (ref "JP1") (pin "3") (pinfunction "VCC_3") (pintype "passive"))
      (node (ref "U1") (pin "3") (pinfunction "VIN_3") (pintype "bidirectional"))
    )
    (net (code "45") (name "GND") (class "Default")
      (node (ref "A1") (pin "GND_1") (pinfunction "GND_GND_1") (pintype "power_in"))
      (node (ref "A1") (pin "GND_2") (pinfunction "GND_GND_2") (pintype "power_in"))
      (node (ref "A1") (pin "GND_3") (pinfunction "GND_GND_3") (pintype "power_in"))
      (node (ref "A1") (pin "GND_4") (pinfunction "GND_GND_4") (pintype "power_in"))
      (node (ref "B2") (pin "2") (pinfunction "GND_1_2") (pintype "bidirectional"))
      (node (ref "B2") (pin "5") (pinfunction "GND_2_5") (pintype "bidirectional"))
      (node (ref "B2") (pin "6") (pinfunction "NC_6") (pintype "bidirectional"))
      (node (ref "BUT1") (pin "2@1") (pinfunction "2_2@1") (pintype "bidirectional"))
      (node (ref "BUT1") (pin "2@2") (pinfunction "2_2@2") (pintype "bidirectional"))
      (node (ref "C1") (pin "1") (pinfunction "1_1") (pintype "passive"))
      (node (ref "C15") (pin "1") (pinfunction "1_1") (pintype "passive"))
      (node (ref "C16") (pin "1") (pinfunction "1_1") (pintype "passive"))
      (node (ref "C17") (pin "1") (pinfunction "1_1") (pintype "passive"))
      (node (ref "C18") (pin "1") (pinfunction "1_1") (pintype "passive"))
      (node (ref "C19") (pin "2") (pinfunction "2_2") (pintype "passive"))
      (node (ref "C2") (pin "1") (pinfunction "1_1") (pintype "passive"))
      (node (ref "C20") (pin "2") (pinfunction "2_2") (pintype "passive"))
      (node (ref "C21") (pin "2") (pinfunction "2_2") (pintype "passive"))
      (node (ref "C22") (pin "1") (pinfunction "1_1") (pintype "passive"))
      (node (ref "C23") (pin "1") (pinfunction "1_1") (pintype "passive"))
      (node (ref "DC2") (pin "1") (pinfunction "1_1") (pintype "passive"))
      (node (ref "DC4") (pin "1") (pinfunction "1_1") (pintype "passive"))
      (node (ref "DC6") (pin "1") (pinfunction "1_1") (pintype "passive"))
      (node (ref "DC8") (pin "1") (pinfunction "1_1") (pintype "passive"))
      (node (ref "J1") (pin "11") (pinfunction "GND/TGTPWR+CAP_11") (pintype "bidirectional"))
      (node (ref "J1") (pin "13") (pinfunction "GND/TGTPWR+CAP2_13") (pintype "bidirectional"))
      (node (ref "J1") (pin "15") (pinfunction "GND3_15") (pintype "bidirectional"))
      (node (ref "J1") (pin "17") (pinfunction "GND4_17") (pintype "bidirectional"))
      (node (ref "J1") (pin "19") (pinfunction "GND5_19") (pintype "bidirectional"))
      (node (ref "J1") (pin "3") (pinfunction "GND1_3") (pintype "bidirectional"))
      (node (ref "J1") (pin "5") (pinfunction "GND2_5") (pintype "bidirectional"))
      (node (ref "J2") (pin "8") (pinfunction "GND_8") (pintype "bidirectional"))
      (node (ref "JP1") (pin "1") (pinfunction "GND_1") (pintype "passive"))
      (node (ref "TP32") (pin "P$1") (pinfunction "P$1_P$1") (pintype "bidirectional"))
      (node (ref "TP33") (pin "P$1") (pinfunction "P$1_P$1") (pintype "bidirectional"))
      (node (ref "TP34") (pin "P$1") (pinfunction "P$1_P$1") (pintype "bidirectional"))
      (node (ref "TP35") (pin "P$1") (pinfunction "P$1_P$1") (pintype "bidirectional"))
      (node (ref "TP36") (pin "P$1") (pinfunction "P$1_P$1") (pintype "bidirectional"))
      (node (ref "TP39") (pin "P$1") (pinfunction "P$1_P$1") (pintype "bidirectional"))
      (node (ref "TP40") (pin "P$1") (pinfunction "P$1_P$1") (pintype "bidirectional"))
      (node (ref "TP41") (pin "P$1") (pinfunction "P$1_P$1") (pintype "bidirectional"))
      (node (ref "TP42") (pin "P$1") (pinfunction "P$1_P$1") (pintype "bidirectional"))
      (node (ref "TP43") (pin "P$1") (pinfunction "P$1_P$1") (pintype "bidirectional"))
      (node (ref "TP44") (pin "P$1") (pinfunction "P$1_P$1") (pintype "bidirectional"))
      (node (ref "TP45") (pin "P$1") (pinfunction "P$1_P$1") (pintype "bidirectional"))
      (node (ref "TP46") (pin "P$1") (pinfunction "P$1_P$1") (pintype "bidirectional"))
      (node (ref "TP47") (pin "P$1") (pinfunction "P$1_P$1") (pintype "bidirectional"))
      (node (ref "TP48") (pin "P$1") (pinfunction "P$1_P$1") (pintype "bidirectional"))
      (node (ref "TP49") (pin "P$1") (pinfunction "P$1_P$1") (pintype "bidirectional"))
      (node (ref "TP50") (pin "P$1") (pinfunction "P$1_P$1") (pintype "bidirectional"))
      (node (ref "TP51") (pin "P$1") (pinfunction "P$1_P$1") (pintype "bidirectional"))
      (node (ref "TP52") (pin "P$1") (pinfunction "P$1_P$1") (pintype "bidirectional"))
      (node (ref "TP53") (pin "P$1") (pinfunction "P$1_P$1") (pintype "bidirectional"))
      (node (ref "TP54") (pin "P$1") (pinfunction "P$1_P$1") (pintype "bidirectional"))
      (node (ref "TP55") (pin "P$1") (pinfunction "P$1_P$1") (pintype "bidirectional"))
      (node (ref "TP56") (pin "P$1") (pinfunction "P$1_P$1") (pintype "bidirectional"))
      (node (ref "TP57") (pin "P$1") (pinfunction "P$1_P$1") (pintype "bidirectional"))
      (node (ref "TP58") (pin "P$1") (pinfunction "P$1_P$1") (pintype "bidirectional"))
      (node (ref "TP59") (pin "P$1") (pinfunction "P$1_P$1") (pintype "bidirectional"))
      (node (ref "TP60") (pin "P$1") (pinfunction "P$1_P$1") (pintype "bidirectional"))
      (node (ref "TP61") (pin "P$1") (pinfunction "P$1_P$1") (pintype "bidirectional"))
      (node (ref "TP63") (pin "2") (pinfunction "P$1_2") (pintype "bidirectional"))
      (node (ref "TP64") (pin "2") (pinfunction "P$1_2") (pintype "bidirectional"))
      (node (ref "TP65") (pin "2") (pinfunction "P$1_2") (pintype "bidirectional"))
      (node (ref "U1") (pin "1") (pinfunction "GND_1") (pintype "bidirectional"))
      (node (ref "U3") (pin "12") (pinfunction "DVSS_2_12") (pintype "bidirectional"))
      (node (ref "U3") (pin "16") (pinfunction "DVSS_3_16") (pintype "bidirectional"))
      (node (ref "U3") (pin "18") (pinfunction "DVSS_4_18") (pintype "bidirectional"))
      (node (ref "U3") (pin "21") (pinfunction "DVSS_5_21") (pintype "bidirectional"))
      (node (ref "U3") (pin "27") (pinfunction "AVSS_3_27") (pintype "bidirectional"))
      (node (ref "U3") (pin "3") (pinfunction "AVSS_1_3") (pintype "bidirectional"))
      (node (ref "U3") (pin "30") (pinfunction "AVSS_4_30") (pintype "bidirectional"))
      (node (ref "U3") (pin "31") (pinfunction "AVSS_5_31") (pintype "bidirectional"))
      (node (ref "U3") (pin "32") (pinfunction "AVSS_6_32") (pintype "bidirectional"))
      (node (ref "U3") (pin "6") (pinfunction "AVSS_2_6") (pintype "bidirectional"))
      (node (ref "U3") (pin "7") (pinfunction "DVSS_1_7") (pintype "bidirectional"))
      (node (ref "U3") (pin "PAD") (pinfunction "AVSS(PAD)_PAD") (pintype "bidirectional"))
      (node (ref "U4") (pin "12") (pinfunction "REFN_12") (pintype "bidirectional"))
      (node (ref "U4") (pin "24") (pinfunction "VSS_1_24") (pintype "bidirectional"))
      (node (ref "U4") (pin "33") (pinfunction "VSS_2_33") (pintype "bidirectional"))
      (node (ref "U4") (pin "43") (pinfunction "VSS_3_43") (pintype "bidirectional"))
      (node (ref "U4") (pin "57") (pinfunction "VSS_4_57") (pintype "bidirectional"))
      (node (ref "U4") (pin "66") (pinfunction "VSS_5_66") (pintype "bidirectional"))
      (node (ref "U4") (pin "78") (pinfunction "VSS_6_78") (pintype "bidirectional"))
      (node (ref "U4") (pin "9") (pinfunction "AVSS_9") (pintype "bidirectional"))
      (node (ref "U5") (pin "2") (pinfunction "GND_2") (pintype "bidirectional"))
    )
    (net (code "46") (name "Net-(A1A-P$1)") (class "Default")
      (node (ref "A1") (pin "CON") (pinfunction "P$1_CON") (pintype "bidirectional"))
      (node (ref "C27") (pin "2") (pinfunction "2_2") (pintype "passive"))
    )
    (net (code "47") (name "Net-(A2-P$1)") (class "Default")
      (node (ref "A2") (pin "CON") (pinfunction "P$1_CON") (pintype "bidirectional"))
      (node (ref "C26") (pin "2") (pinfunction "2_2") (pintype "passive"))
    )
    (net (code "48") (name "Net-(B2-RFN)") (class "Default")
      (node (ref "B2") (pin "3") (pinfunction "RFN_3") (pintype "bidirectional"))
      (node (ref "C14") (pin "2") (pinfunction "2_2") (pintype "passive"))
    )
    (net (code "49") (name "Net-(B2-RFP)") (class "Default")
      (node (ref "B2") (pin "4") (pinfunction "RFP_4") (pintype "bidirectional"))
      (node (ref "C13") (pin "2") (pinfunction "2_2") (pintype "passive"))
    )
    (net (code "50") (name "Net-(B2-RF_UNB)") (class "Default")
      (node (ref "B2") (pin "1") (pinfunction "RF_UNB_1") (pintype "bidirectional"))
      (node (ref "C25") (pin "1") (pinfunction "1_1") (pintype "passive"))
    )
    (net (code "51") (name "Net-(U3-AVDD)") (class "Default")
      (node (ref "C20") (pin "1") (pinfunction "1_1") (pintype "passive"))
      (node (ref "U3") (pin "29") (pinfunction "AVDD_29") (pintype "bidirectional"))
    )
    (net (code "52") (name "Net-(U3-DVDD_1)") (class "Default")
      (node (ref "C19") (pin "1") (pinfunction "1_1") (pintype "passive"))
      (node (ref "U3") (pin "13") (pinfunction "DVDD_1_13") (pintype "bidirectional"))
      (node (ref "U3") (pin "14") (pinfunction "DVDD_2_14") (pintype "bidirectional"))
    )
    (net (code "53") (name "Net-(U3-RFN)") (class "Default")
      (node (ref "C14") (pin "1") (pinfunction "1_1") (pintype "passive"))
      (node (ref "U3") (pin "5") (pinfunction "RFN_5") (pintype "bidirectional"))
    )
    (net (code "54") (name "Net-(U3-RFP)") (class "Default")
      (node (ref "C13") (pin "1") (pinfunction "1_1") (pintype "passive"))
      (node (ref "U3") (pin "4") (pinfunction "RFP_4") (pintype "bidirectional"))
    )
    (net (code "55") (name "Net-(U3-XTAL1)") (class "Default")
      (node (ref "C15") (pin "2") (pinfunction "2_2") (pintype "passive"))
      (node (ref "U3") (pin "26") (pinfunction "XTAL1_26") (pintype "bidirectional"))
      (node (ref "X4") (pin "3") (pinfunction "A_3") (pintype "bidirectional"))
    )
    (net (code "56") (name "Net-(U3-XTAL2)") (class "Default")
      (node (ref "C16") (pin "2") (pinfunction "2_2") (pintype "passive"))
      (node (ref "U3") (pin "25") (pinfunction "XTAL2_25") (pintype "bidirectional"))
      (node (ref "X4") (pin "1") (pinfunction "B_1") (pintype "bidirectional"))
    )
    (net (code "57") (name "Net-(U4-AVDD)") (class "Default")
      (node (ref "DC2") (pin "2") (pinfunction "2_2") (pintype "passive"))
      (node (ref "L1") (pin "1") (pinfunction "1_1") (pintype "passive"))
      (node (ref "U4") (pin "8") (pinfunction "AVDD_8") (pintype "bidirectional"))
    )
    (net (code "58") (name "Net-(U4-RTCX1)") (class "Default")
      (node (ref "C22") (pin "2") (pinfunction "2_2") (pintype "passive"))
      (node (ref "U4") (pin "13") (pinfunction "RTCX1_13") (pintype "bidirectional"))
      (node (ref "X3") (pin "1") (pinfunction "A_1") (pintype "bidirectional"))
    )
    (net (code "59") (name "Net-(U4-RTCX2)") (class "Default")
      (node (ref "C23") (pin "2") (pinfunction "2_2") (pintype "passive"))
      (node (ref "U4") (pin "15") (pinfunction "RTCX2_15") (pintype "bidirectional"))
      (node (ref "X3") (pin "2") (pinfunction "B_2") (pintype "bidirectional"))
    )
    (net (code "60") (name "Net-(U4-XTAL1)") (class "Default")
      (node (ref "C24") (pin "1") (pinfunction "1_1") (pintype "passive"))
      (node (ref "U4") (pin "19") (pinfunction "XTAL1_19") (pintype "bidirectional"))
    )
    (net (code "61") (name "Net-(U5-A)") (class "Default")
      (node (ref "C27") (pin "1") (pinfunction "1_1") (pintype "passive"))
      (node (ref "U5") (pin "1") (pinfunction "A_1") (pintype "bidirectional"))
    )
    (net (code "62") (name "Net-(U5-B)") (class "Default")
      (node (ref "C26") (pin "1") (pinfunction "1_1") (pintype "passive"))
      (node (ref "U5") (pin "3") (pinfunction "B_3") (pintype "bidirectional"))
    )
    (net (code "63") (name "Net-(U5-W)") (class "Default")
      (node (ref "C25") (pin "2") (pinfunction "2_2") (pintype "passive"))
      (node (ref "U5") (pin "5") (pinfunction "W_5") (pintype "bidirectional"))
    )
    (net (code "64") (name "unconnected-(J1-GNDDETECT-Pad9)") (class "Default")
      (node (ref "J1") (pin "9") (pinfunction "GNDDETECT_9") (pintype "bidirectional"))
    )
    (net (code "65") (name "unconnected-(J1-KEY-Pad7)") (class "Default")
      (node (ref "J1") (pin "7") (pinfunction "KEY_7") (pintype "bidirectional"))
    )
    (net (code "66") (name "unconnected-(JP1-CTS-Pad2)") (class "Default")
      (node (ref "JP1") (pin "2") (pinfunction "CTS_2") (pintype "passive"))
    )
    (net (code "67") (name "unconnected-(U4-#RSTOUT-Pad11)") (class "Default")
      (node (ref "U4") (pin "11") (pinfunction "#RSTOUT_11") (pintype "bidirectional"))
    )
    (net (code "68") (name "unconnected-(U4-#TRST-Pad4)") (class "Default")
      (node (ref "U4") (pin "4") (pinfunction "#TRST_4") (pintype "bidirectional"))
    )
    (net (code "69") (name "unconnected-(U4-P0[10]{slash}TXD2{slash}SDA2{slash}MAT3[0]-Pad39)") (class "Default")
      (node (ref "U4") (pin "39") (pinfunction "P0[10]/TXD2/SDA2/MAT3[0]_39") (pintype "bidirectional"))
    )
    (net (code "70") (name "unconnected-(U4-P0[11]{slash}RXD2{slash}SCL2{slash}MAT3[1]-Pad40)") (class "Default")
      (node (ref "U4") (pin "40") (pinfunction "P0[11]/RXD2/SCL2/MAT3[1]_40") (pintype "bidirectional"))
    )
    (net (code "71") (name "unconnected-(U4-P0[15]{slash}TXD1{slash}SCK0{slash}SCK-Pad47)") (class "Default")
      (node (ref "U4") (pin "47") (pinfunction "P0[15]/TXD1/SCK0/SCK_47") (pintype "bidirectional"))
    )
    (net (code "72") (name "unconnected-(U4-P0[16]{slash}RXD1{slash}SSEL0{slash}SSEL-Pad48)") (class "Default")
      (node (ref "U4") (pin "48") (pinfunction "P0[16]/RXD1/SSEL0/SSEL_48") (pintype "bidirectional"))
    )
    (net (code "73") (name "unconnected-(U4-P0[18]{slash}DCD1{slash}MOSI0{slash}MOSI-Pad45)") (class "Default")
      (node (ref "U4") (pin "45") (pinfunction "P0[18]/DCD1/MOSI0/MOSI_45") (pintype "bidirectional"))
    )
    (net (code "74") (name "unconnected-(U4-P0[29]{slash}USB_D+-Pad22)") (class "Default")
      (node (ref "U4") (pin "22") (pinfunction "P0[29]/USB_D+_22") (pintype "bidirectional"))
    )
    (net (code "75") (name "unconnected-(U4-P0[30]{slash}USB_D--Pad23)") (class "Default")
      (node (ref "U4") (pin "23") (pinfunction "P0[30]/USB_D-_23") (pintype "bidirectional"))
    )
    (net (code "76") (name "unconnected-(U4-P1[4]{slash}ENET_TX_EN-Pad74)") (class "Default")
      (node (ref "U4") (pin "74") (pinfunction "P1[4]/ENET_TX_EN_74") (pintype "bidirectional"))
    )
    (net (code "77") (name "unconnected-(U4-P1[8]{slash}ENET_CRS-Pad73)") (class "Default")
      (node (ref "U4") (pin "73") (pinfunction "P1[8]/ENET_CRS_73") (pintype "bidirectional"))
    )
    (net (code "78") (name "unconnected-(U4-P1[9]{slash}ENET_RXD0-Pad72)") (class "Default")
      (node (ref "U4") (pin "72") (pinfunction "P1[9]/ENET_RXD0_72") (pintype "bidirectional"))
    )
    (net (code "79") (name "unconnected-(U4-P1[10]{slash}ENET_RXD1-Pad71)") (class "Default")
      (node (ref "U4") (pin "71") (pinfunction "P1[10]/ENET_RXD1_71") (pintype "bidirectional"))
    )
    (net (code "80") (name "unconnected-(U4-P1[14]{slash}ENET_RX_ER-Pad70)") (class "Default")
      (node (ref "U4") (pin "70") (pinfunction "P1[14]/ENET_RX_ER_70") (pintype "bidirectional"))
    )
    (net (code "81") (name "unconnected-(U4-P1[15]{slash}ENET_REF_CLK-Pad69)") (class "Default")
      (node (ref "U4") (pin "69") (pinfunction "P1[15]/ENET_REF_CLK_69") (pintype "bidirectional"))
    )
    (net (code "82") (name "unconnected-(U4-P1[25]{slash}MCOA1{slash}MAT1[1]-Pad31)") (class "Default")
      (node (ref "U4") (pin "31") (pinfunction "P1[25]/MCOA1/MAT1[1]_31") (pintype "bidirectional"))
    )
    (net (code "83") (name "unconnected-(U4-P1[28]{slash}MCOA2{slash}PCAP1[0]{slash}MAT0[0]-Pad35)") (class "Default")
      (node (ref "U4") (pin "35") (pinfunction "P1[28]/MCOA2/PCAP1[0]/MAT0[0]_35") (pintype "bidirectional"))
    )
    (net (code "84") (name "unconnected-(U4-P2[8]{slash}TD2{slash}TXD2-Pad50)") (class "Default")
      (node (ref "U4") (pin "50") (pinfunction "P2[8]/TD2/TXD2_50") (pintype "bidirectional"))
    )
    (net (code "85") (name "unconnected-(U4-P2[9]{slash}USB_CONNECT{slash}RXD2-Pad49)") (class "Default")
      (node (ref "U4") (pin "49") (pinfunction "P2[9]/USB_CONNECT/RXD2_49") (pintype "bidirectional"))
    )
    (net (code "86") (name "unconnected-(U4-P4[28]{slash}RX_MCLK{slash}MAT2[0]{slash}TXD3-Pad65)") (class "Default")
      (node (ref "U4") (pin "65") (pinfunction "P4[28]/RX_MCLK/MAT2[0]/TXD3_65") (pintype "bidirectional"))
    )
    (net (code "87") (name "unconnected-(U4-P4[29]{slash}TX_MCLK{slash}MAT2[1]{slash}RXD3-Pad68)") (class "Default")
      (node (ref "U4") (pin "68") (pinfunction "P4[29]/TX_MCLK/MAT2[1]/RXD3_68") (pintype "bidirectional"))
    )
    (net (code "88") (name "unconnected-(U4-VBAT-Pad16)") (class "Default")
      (node (ref "U4") (pin "16") (pinfunction "VBAT_16") (pintype "bidirectional"))
    )
    (net (code "89") (name "unconnected-(U4-XTAL2-Pad20)") (class "Default")
      (node (ref "U4") (pin "20") (pinfunction "XTAL2_20") (pintype "bidirectional"))
    )
  )
)
